# PSU_TPS75501_3V8.net
KiCad netlist of a schematic drawn in Altium Designer
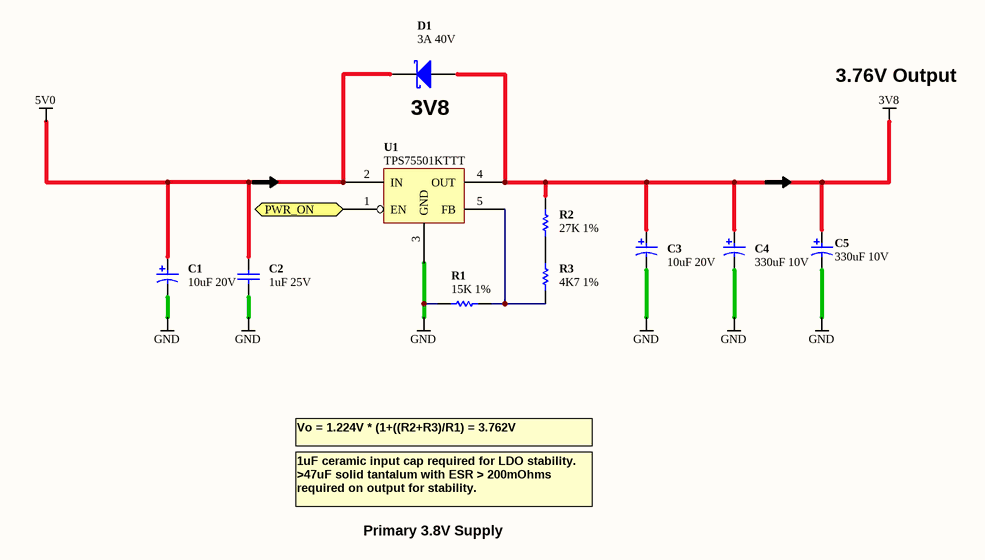
[diagram p0: PSU_TPS75501_3V8.SchDoc]

(export (version "E")
  (design (tool "Eeschema 10.0.6"))
  (components
    (comp (ref "C1")
      (value "10uF 20V")
      (footprint "CAPC3528-STAR")
      (description "Capacitor, Tantalum, 10uF 10% 20V MCCT-B (3528)")
      (fields (field (name "TOLERANCE") "10 %"))
      (libsource (lib "AltiumDesignLibrary") (part "CAP-P"))
    )
    (comp (ref "C2")
      (value "1uF 25V")
      (footprint "CAPC3216-STAR")
      (description "Capacitor, Ceramic, 1uF 10% 25V 1206 (3216) X7R")
      (fields (field (name "TOLERANCE") "10 %"))
      (libsource (lib "AltiumDesignLibrary") (part "CAP-NP"))
    )
    (comp (ref "C3")
      (value "10uF 20V")
      (footprint "CAPC3528-STAR")
      (description "Capacitor, Tantalum, 10uF 10% 20V MCCT-B (3528)")
      (fields (field (name "TOLERANCE") "10 %"))
      (libsource (lib "AltiumDesignLibrary") (part "CAP-P"))
    )
    (comp (ref "C4")
      (value "330uF 10V")
      (footprint "CAPC7343-STAR")
      (description "Capacitor, Tantalum, 330uF 20% 10V, LOW ESR 6mR MCCT-D (7343-31)")
      (fields (field (name "TOLERANCE") "20 %"))
      (libsource (lib "AltiumDesignLibrary") (part "CAP-P"))
    )
    (comp (ref "C5")
      (value "330uF 10V")
      (footprint "CAPC7343-STAR")
      (description "Capacitor, Tantalum, 330uF 20% 10V, LOW ESR 6mR MCCT-D (7343-31)")
      (fields (field (name "TOLERANCE") "20 %"))
      (libsource (lib "AltiumDesignLibrary") (part "CAP-P"))
    )
    (comp (ref "D1")
      (value "3A 40V")
      (footprint "DIOM5027")
      (description "Schottky Diode, 3A 40V")
      (libsource (lib "AltiumDesignLibrary") (part "DIO-SCHOTTKY-1S"))
    )
    (comp (ref "R1")
      (value "15K 1%")
      (footprint "RESC1005-STAR")
      (description "Resistor, 15K 1% 0402 (1005)")
      (fields (field (name "TOLERANCE") "1 %"))
      (libsource (lib "AltiumDesignLibrary") (part "RES"))
    )
    (comp (ref "R2")
      (value "27K 1%")
      (footprint "RESC1005-STAR")
      (description "Resistor, 27K 1% 0402 (1005)")
      (fields (field (name "TOLERANCE") "1 %"))
      (libsource (lib "AltiumDesignLibrary") (part "RES"))
    )
    (comp (ref "R3")
      (value "4K7 1%")
      (footprint "RESC1005-STAR")
      (description "Resistor, 4K7 1% 0402 (1005)")
      (fields (field (name "TOLERANCE") "1 %"))
      (libsource (lib "AltiumDesignLibrary") (part "RES"))
    )
    (comp (ref "U1")
      (value "TPS75501KTTT")
      (footprint "TO-263")
      (description "TPS75501KTTT, 5A, Low Dropout, Adjustable, Linear Voltage Regulator, TO-263")
      (libsource (lib "AltiumDesignLibrary") (part "TPS75501"))
    )
  )
  (nets
    (net (code "1") (name "/PWR_ON") (class "Default")
      (node (ref "U1") (pin "1") (pinfunction "EN_1") (pintype "passive"))
    )
    (net (code "2") (name "3V8") (class "Default")
      (node (ref "C3") (pin "1") (pinfunction "1_1") (pintype "passive"))
      (node (ref "C4") (pin "1") (pinfunction "1_1") (pintype "passive"))
      (node (ref "C5") (pin "1") (pinfunction "1_1") (pintype "passive"))
      (node (ref "D1") (pin "1") (pinfunction "A_1") (pintype "passive"))
      (node (ref "R2") (pin "2") (pinfunction "2_2") (pintype "passive"))
      (node (ref "U1") (pin "4") (pinfunction "OUT_4") (pintype "passive"))
    )
    (net (code "3") (name "5V0") (class "Default")
      (node (ref "C1") (pin "1") (pinfunction "1_1") (pintype "passive"))
      (node (ref "C2") (pin "1") (pinfunction "1_1") (pintype "passive"))
      (node (ref "D1") (pin "2") (pinfunction "K_2") (pintype "passive"))
      (node (ref "U1") (pin "2") (pinfunction "IN_2") (pintype "passive"))
    )
    (net (code "4") (name "GND") (class "Default")
      (node (ref "C1") (pin "2") (pinfunction "2_2") (pintype "passive"))
      (node (ref "C2") (pin "2") (pinfunction "2_2") (pintype "passive"))
      (node (ref "C3") (pin "2") (pinfunction "2_2") (pintype "passive"))
      (node (ref "C4") (pin "2") (pinfunction "2_2") (pintype "passive"))
      (node (ref "C5") (pin "2") (pinfunction "2_2") (pintype "passive"))
      (node (ref "R1") (pin "1") (pinfunction "1_1") (pintype "passive"))
      (node (ref "U1") (pin "3") (pinfunction "GND_3") (pintype "passive"))
    )
    (net (code "5") (name "Net-(R2-Pad1)") (class "Default")
      (node (ref "R2") (pin "1") (pinfunction "1_1") (pintype "passive"))
      (node (ref "R3") (pin "2") (pinfunction "2_2") (pintype "passive"))
    )
    (net (code "6") (name "Net-(U1-FB)") (class "Default")
      (node (ref "R1") (pin "2") (pinfunction "2_2") (pintype "passive"))
      (node (ref "R3") (pin "1") (pinfunction "1_1") (pintype "passive"))
      (node (ref "U1") (pin "5") (pinfunction "FB_5") (pintype "passive"))
    )
  )
)
